# m202-stereo-input.net
KiCad netlist of a schematic drawn in EAGLE
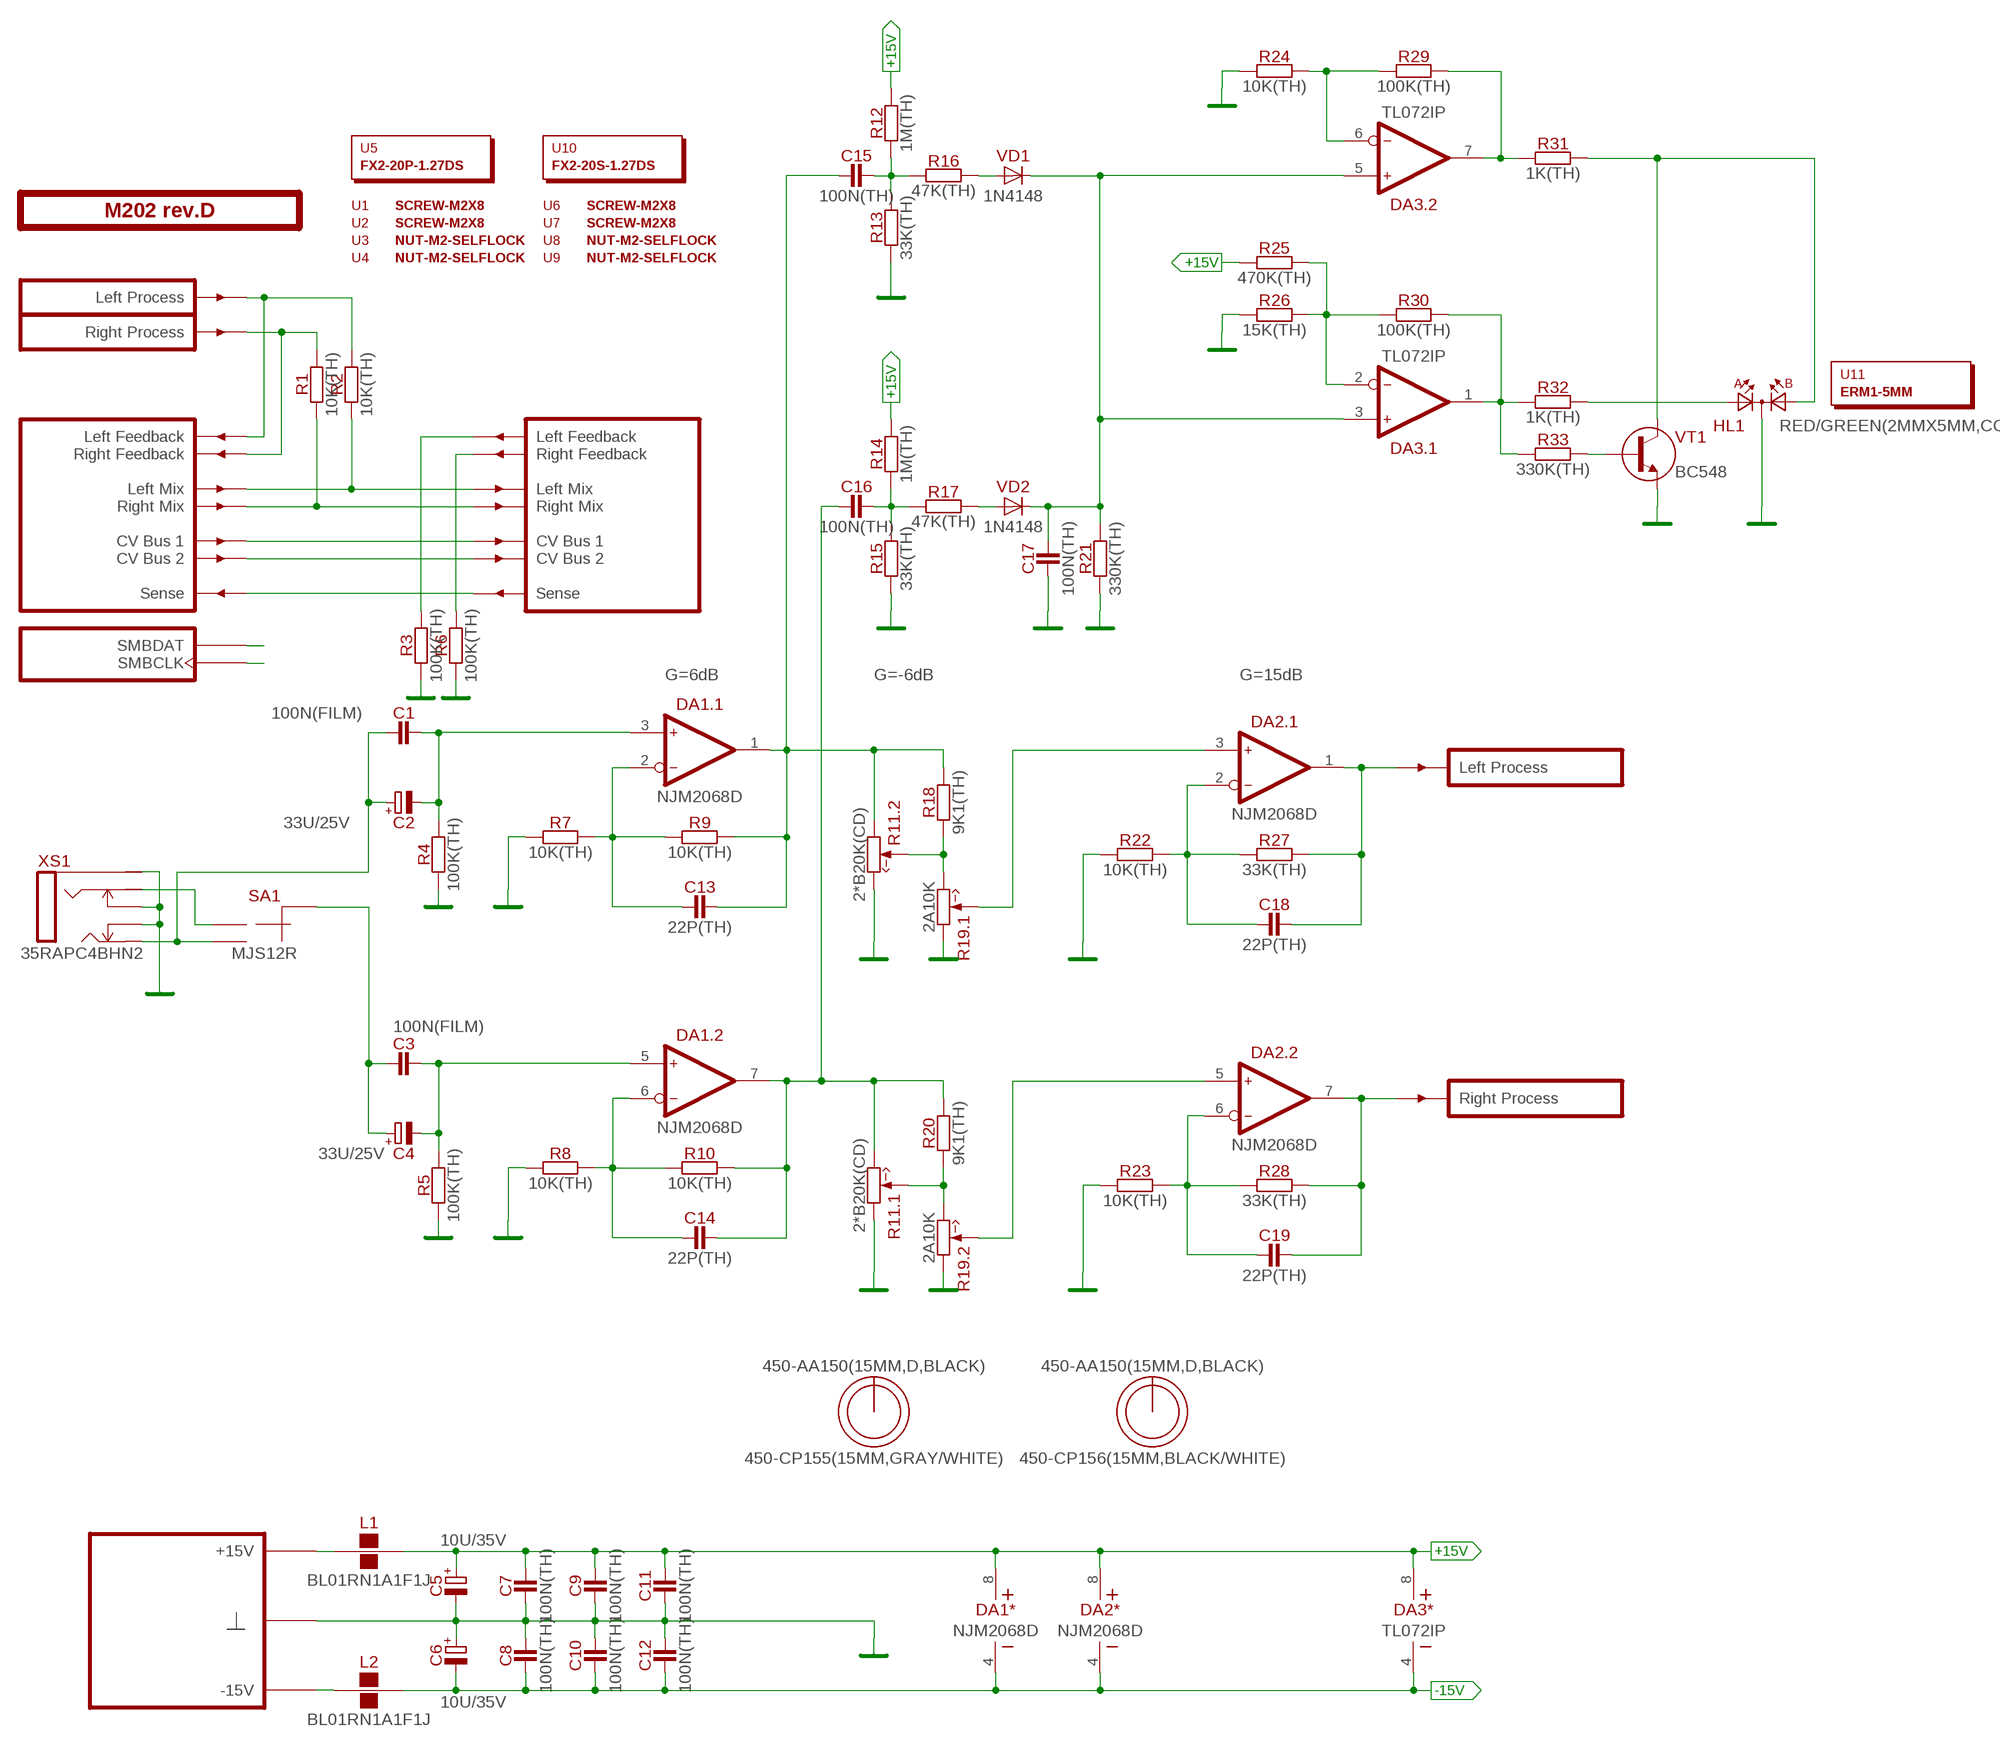
[diagram p0: schematic, sheet 1]

(export (version "E")
  (design (tool "Eeschema 10.0.6"))
  (components
    (comp (ref "C1")
      (value "100N(FILM)")
      (footprint "eagle-import:C050-025X075")
      (libsource (lib "eagle-import") (part "?100N(FILM)"))
    )
    (comp (ref "C2")
      (value "33U/25V")
      (footprint "eagle-import:E2,5-7")
      (libsource (lib "eagle-import") (part "?33U/25V"))
    )
    (comp (ref "C3")
      (value "100N(FILM)")
      (footprint "eagle-import:C050-025X075")
      (libsource (lib "eagle-import") (part "?100N(FILM)"))
    )
    (comp (ref "C4")
      (value "33U/25V")
      (footprint "eagle-import:E2,5-7")
      (libsource (lib "eagle-import") (part "?33U/25V"))
    )
    (comp (ref "C5")
      (value "10U/35V")
      (footprint "eagle-import:E2-5")
      (libsource (lib "eagle-import") (part "?10U/35V"))
    )
    (comp (ref "C6")
      (value "10U/35V")
      (footprint "eagle-import:E2-5")
      (libsource (lib "eagle-import") (part "?10U/35V"))
    )
    (comp (ref "C7")
      (value "100N(TH)")
      (footprint "eagle-import:C050-024X044")
      (libsource (lib "eagle-import") (part "?100N(TH)"))
    )
    (comp (ref "C8")
      (value "100N(TH)")
      (footprint "eagle-import:C050-024X044")
      (libsource (lib "eagle-import") (part "?100N(TH)"))
    )
    (comp (ref "C9")
      (value "100N(TH)")
      (footprint "eagle-import:C050-024X044")
      (libsource (lib "eagle-import") (part "?100N(TH)"))
    )
    (comp (ref "C10")
      (value "100N(TH)")
      (footprint "eagle-import:C050-024X044")
      (libsource (lib "eagle-import") (part "?100N(TH)"))
    )
    (comp (ref "C11")
      (value "100N(TH)")
      (footprint "eagle-import:C050-024X044")
      (libsource (lib "eagle-import") (part "?100N(TH)"))
    )
    (comp (ref "C12")
      (value "100N(TH)")
      (footprint "eagle-import:C050-024X044")
      (libsource (lib "eagle-import") (part "?100N(TH)"))
    )
    (comp (ref "C13")
      (value "22P(TH)")
      (footprint "eagle-import:C050-024X044")
      (libsource (lib "eagle-import") (part "?22P(TH)"))
    )
    (comp (ref "C14")
      (value "22P(TH)")
      (footprint "eagle-import:C050-024X044")
      (libsource (lib "eagle-import") (part "?22P(TH)"))
    )
    (comp (ref "C15")
      (value "100N(TH)")
      (footprint "eagle-import:C050-024X044")
      (libsource (lib "eagle-import") (part "?100N(TH)"))
    )
    (comp (ref "C16")
      (value "100N(TH)")
      (footprint "eagle-import:C050-024X044")
      (libsource (lib "eagle-import") (part "?100N(TH)"))
    )
    (comp (ref "C17")
      (value "100N(TH)")
      (footprint "eagle-import:C050-024X044")
      (libsource (lib "eagle-import") (part "?100N(TH)"))
    )
    (comp (ref "C18")
      (value "22P(TH)")
      (footprint "eagle-import:C050-024X044")
      (libsource (lib "eagle-import") (part "?22P(TH)"))
    )
    (comp (ref "C19")
      (value "22P(TH)")
      (footprint "eagle-import:C050-024X044")
      (libsource (lib "eagle-import") (part "?22P(TH)"))
    )
    (comp (ref "DA1")
      (value "NJM2068D")
      (footprint "eagle-import:DIP-8")
      (libsource (lib "eagle-import") (part "NJM2068D"))
    )
    (comp (ref "DA2")
      (value "NJM2068D")
      (footprint "eagle-import:DIP-8")
      (libsource (lib "eagle-import") (part "NJM2068D"))
    )
    (comp (ref "DA3")
      (value "TL072IP")
      (footprint "eagle-import:DIP-8")
      (libsource (lib "eagle-import") (part "TL072IP"))
    )
    (comp (ref "HL1")
      (value "RED/GREEN(2MMX5MM,CC)")
      (footprint "eagle-import:LED2X5-3PIN")
      (libsource (lib "eagle-import") (part "?(2MMX5MM,CC)RED/GREEN"))
    )
    (comp (ref "L1")
      (value "BL01RN1A1F1J")
      (footprint "eagle-import:BL01RN1A")
      (libsource (lib "eagle-import") (part "BL01RN1A?1F1J"))
    )
    (comp (ref "L2")
      (value "BL01RN1A1F1J")
      (footprint "eagle-import:BL01RN1A")
      (libsource (lib "eagle-import") (part "BL01RN1A?1F1J"))
    )
    (comp (ref "O1")
      (value "450-AA150(15MM,D,BLACK)")
      (footprint "eagle-import:EMPTY")
      (libsource (lib "eagle-import") (part "450-AA?150(15MM,D,BLACK)"))
    )
    (comp (ref "O2")
      (value "450-CP155(15MM,GRAY/WHITE)")
      (footprint "eagle-import:EMPTY")
      (libsource (lib "eagle-import") (part "450-C?P155(15MM,GRAY/WHITE)"))
    )
    (comp (ref "O3")
      (value "450-AA150(15MM,D,BLACK)")
      (footprint "eagle-import:EMPTY")
      (libsource (lib "eagle-import") (part "450-AA?150(15MM,D,BLACK)"))
    )
    (comp (ref "O4")
      (value "450-CP156(15MM,BLACK/WHITE)")
      (footprint "eagle-import:EMPTY")
      (libsource (lib "eagle-import") (part "450-C?P156(15MM,BLACK/WHITE)"))
    )
    (comp (ref "PCB1")
      (value "M202 rev.D")
      (footprint "eagle-import:ST2-BOARD-50")
      (libsource (lib "eagle-import") (part "ST2-BOARD-?50"))
    )
    (comp (ref "R1")
      (value "10K(TH)")
      (footprint "eagle-import:R-0207_10")
      (libsource (lib "eagle-import") (part "?10K(TH)"))
    )
    (comp (ref "R2")
      (value "10K(TH)")
      (footprint "eagle-import:R-0207_10")
      (libsource (lib "eagle-import") (part "?10K(TH)"))
    )
    (comp (ref "R3")
      (value "100K(TH)")
      (footprint "eagle-import:R-0207_10")
      (libsource (lib "eagle-import") (part "?100K(TH)"))
    )
    (comp (ref "R4")
      (value "100K(TH)")
      (footprint "eagle-import:R-0207_10")
      (libsource (lib "eagle-import") (part "?100K(TH)"))
    )
    (comp (ref "R5")
      (value "100K(TH)")
      (footprint "eagle-import:R-0207_10")
      (libsource (lib "eagle-import") (part "?100K(TH)"))
    )
    (comp (ref "R6")
      (value "100K(TH)")
      (footprint "eagle-import:R-0207_10")
      (libsource (lib "eagle-import") (part "?100K(TH)"))
    )
    (comp (ref "R7")
      (value "10K(TH)")
      (footprint "eagle-import:R-0207_10")
      (libsource (lib "eagle-import") (part "?10K(TH)"))
    )
    (comp (ref "R8")
      (value "10K(TH)")
      (footprint "eagle-import:R-0207_10")
      (libsource (lib "eagle-import") (part "?10K(TH)"))
    )
    (comp (ref "R9")
      (value "10K(TH)")
      (footprint "eagle-import:R-0207_10")
      (libsource (lib "eagle-import") (part "?10K(TH)"))
    )
    (comp (ref "R10")
      (value "10K(TH)")
      (footprint "eagle-import:R-0207_10")
      (libsource (lib "eagle-import") (part "?10K(TH)"))
    )
    (comp (ref "R11")
      (value "2*B20K(CD)")
      (footprint "eagle-import:RV11-DUAL")
      (libsource (lib "eagle-import") (part "2?B20K(CD)"))
    )
    (comp (ref "R12")
      (value "1M(TH)")
      (footprint "eagle-import:R-0207_10")
      (libsource (lib "eagle-import") (part "?1M(TH)"))
    )
    (comp (ref "R13")
      (value "33K(TH)")
      (footprint "eagle-import:R-0207_10")
      (libsource (lib "eagle-import") (part "?33K(TH)"))
    )
    (comp (ref "R14")
      (value "1M(TH)")
      (footprint "eagle-import:R-0207_10")
      (libsource (lib "eagle-import") (part "?1M(TH)"))
    )
    (comp (ref "R15")
      (value "33K(TH)")
      (footprint "eagle-import:R-0207_10")
      (libsource (lib "eagle-import") (part "?33K(TH)"))
    )
    (comp (ref "R16")
      (value "47K(TH)")
      (footprint "eagle-import:R-0207_10")
      (libsource (lib "eagle-import") (part "?47K(TH)"))
    )
    (comp (ref "R17")
      (value "47K(TH)")
      (footprint "eagle-import:R-0207_10")
      (libsource (lib "eagle-import") (part "?47K(TH)"))
    )
    (comp (ref "R18")
      (value "9K1(TH)")
      (footprint "eagle-import:R-0207_10")
      (libsource (lib "eagle-import") (part "?9K1(TH)"))
    )
    (comp (ref "R19")
      (value "2A10K")
      (footprint "eagle-import:RV11-DUAL")
      (libsource (lib "eagle-import") (part "2?A10K"))
    )
    (comp (ref "R20")
      (value "9K1(TH)")
      (footprint "eagle-import:R-0207_10")
      (libsource (lib "eagle-import") (part "?9K1(TH)"))
    )
    (comp (ref "R21")
      (value "330K(TH)")
      (footprint "eagle-import:R-0207_10")
      (libsource (lib "eagle-import") (part "?330K(TH)"))
    )
    (comp (ref "R22")
      (value "10K(TH)")
      (footprint "eagle-import:R-0207_10")
      (libsource (lib "eagle-import") (part "?10K(TH)"))
    )
    (comp (ref "R23")
      (value "10K(TH)")
      (footprint "eagle-import:R-0207_10")
      (libsource (lib "eagle-import") (part "?10K(TH)"))
    )
    (comp (ref "R24")
      (value "10K(TH)")
      (footprint "eagle-import:R-0207_10")
      (libsource (lib "eagle-import") (part "?10K(TH)"))
    )
    (comp (ref "R25")
      (value "470K(TH)")
      (footprint "eagle-import:R-0207_10")
      (libsource (lib "eagle-import") (part "?470K(TH)"))
    )
    (comp (ref "R26")
      (value "15K(TH)")
      (footprint "eagle-import:R-0207_10")
      (libsource (lib "eagle-import") (part "?15K(TH)"))
    )
    (comp (ref "R27")
      (value "33K(TH)")
      (footprint "eagle-import:R-0207_10")
      (libsource (lib "eagle-import") (part "?33K(TH)"))
    )
    (comp (ref "R28")
      (value "33K(TH)")
      (footprint "eagle-import:R-0207_10")
      (libsource (lib "eagle-import") (part "?33K(TH)"))
    )
    (comp (ref "R29")
      (value "100K(TH)")
      (footprint "eagle-import:R-0207_10")
      (libsource (lib "eagle-import") (part "?100K(TH)"))
    )
    (comp (ref "R30")
      (value "100K(TH)")
      (footprint "eagle-import:R-0207_10")
      (libsource (lib "eagle-import") (part "?100K(TH)"))
    )
    (comp (ref "R31")
      (value "1K(TH)")
      (footprint "eagle-import:R-0207_10")
      (libsource (lib "eagle-import") (part "?1K(TH)"))
    )
    (comp (ref "R32")
      (value "1K(TH)")
      (footprint "eagle-import:R-0207_10")
      (libsource (lib "eagle-import") (part "?1K(TH)"))
    )
    (comp (ref "R33")
      (value "330K(TH)")
      (footprint "eagle-import:R-0207_10")
      (libsource (lib "eagle-import") (part "?330K(TH)"))
    )
    (comp (ref "SA1")
      (value "MJS12R")
      (footprint "eagle-import:APEM-MJS12R")
      (libsource (lib "eagle-import") (part "MJS12R"))
    )
    (comp (ref "U1")
      (value "SCREW-M2X8")
      (footprint "eagle-import:EMPTY")
      (libsource (lib "eagle-import") (part "?SCREW-M2X8"))
    )
    (comp (ref "U2")
      (value "SCREW-M2X8")
      (footprint "eagle-import:EMPTY")
      (libsource (lib "eagle-import") (part "?SCREW-M2X8"))
    )
    (comp (ref "U3")
      (value "NUT-M2-SELFLOCK")
      (footprint "eagle-import:EMPTY")
      (libsource (lib "eagle-import") (part "?NUT-M2-SELFLOCK"))
    )
    (comp (ref "U4")
      (value "NUT-M2-SELFLOCK")
      (footprint "eagle-import:EMPTY")
      (libsource (lib "eagle-import") (part "?NUT-M2-SELFLOCK"))
    )
    (comp (ref "U5")
      (value "FX2-20P-1.27DS")
      (footprint "eagle-import:EMPTY")
      (libsource (lib "eagle-import") (part "?FX2-20P-1.27DS"))
    )
    (comp (ref "U6")
      (value "SCREW-M2X8")
      (footprint "eagle-import:EMPTY")
      (libsource (lib "eagle-import") (part "?SCREW-M2X8"))
    )
    (comp (ref "U7")
      (value "SCREW-M2X8")
      (footprint "eagle-import:EMPTY")
      (libsource (lib "eagle-import") (part "?SCREW-M2X8"))
    )
    (comp (ref "U8")
      (value "NUT-M2-SELFLOCK")
      (footprint "eagle-import:EMPTY")
      (libsource (lib "eagle-import") (part "?NUT-M2-SELFLOCK"))
    )
    (comp (ref "U9")
      (value "NUT-M2-SELFLOCK")
      (footprint "eagle-import:EMPTY")
      (libsource (lib "eagle-import") (part "?NUT-M2-SELFLOCK"))
    )
    (comp (ref "U10")
      (value "FX2-20S-1.27DS")
      (footprint "eagle-import:EMPTY")
      (libsource (lib "eagle-import") (part "?FX2-20S-1.27DS"))
    )
    (comp (ref "U11")
      (value "ERM1-5MM")
      (footprint "eagle-import:EMPTY")
      (libsource (lib "eagle-import") (part "?ERM1-5MM"))
    )
    (comp (ref "VD1")
      (value "1N4148")
      (footprint "eagle-import:DO35-7")
      (libsource (lib "eagle-import") (part "?1N4148"))
    )
    (comp (ref "VD2")
      (value "1N4148")
      (footprint "eagle-import:DO35-7")
      (libsource (lib "eagle-import") (part "?1N4148"))
    )
    (comp (ref "VT1")
      (value "BC548")
      (footprint "eagle-import:TO92")
      (libsource (lib "eagle-import") (part "?BC548"))
    )
    (comp (ref "XS1")
      (value "35RAPC4BHN2")
      (footprint "eagle-import:35RAP")
      (libsource (lib "eagle-import") (part "35RAPC4BHN2"))
    )
  )
  (nets
    (net (code "1") (name "+15V") (class "Default")
      (node (ref "C11") (pin "2") (pinfunction "2_2") (pintype "passive"))
      (node (ref "C5") (pin "+") (pinfunction "+_+") (pintype "passive"))
      (node (ref "C7") (pin "2") (pinfunction "2_2") (pintype "passive"))
      (node (ref "C9") (pin "2") (pinfunction "2_2") (pintype "passive"))
      (node (ref "DA1") (pin "8") (pinfunction "V+_8") (pintype "power_in"))
      (node (ref "DA2") (pin "8") (pinfunction "V+_8") (pintype "power_in"))
      (node (ref "DA3") (pin "8") (pinfunction "V+_8") (pintype "power_in"))
      (node (ref "L1") (pin "2") (pinfunction "2_2") (pintype "passive"))
      (node (ref "R12") (pin "2") (pinfunction "2_2") (pintype "passive"))
      (node (ref "R14") (pin "2") (pinfunction "2_2") (pintype "passive"))
      (node (ref "R25") (pin "1") (pinfunction "1_1") (pintype "passive"))
    )
    (net (code "2") (name "-15V") (class "Default")
      (node (ref "C10") (pin "1") (pinfunction "1_1") (pintype "passive"))
      (node (ref "C12") (pin "1") (pinfunction "1_1") (pintype "passive"))
      (node (ref "C6") (pin "-") (pinfunction "-_-") (pintype "passive"))
      (node (ref "C8") (pin "1") (pinfunction "1_1") (pintype "passive"))
      (node (ref "DA1") (pin "4") (pinfunction "V-_4") (pintype "power_in"))
      (node (ref "DA2") (pin "4") (pinfunction "V-_4") (pintype "power_in"))
      (node (ref "DA3") (pin "4") (pinfunction "V-_4") (pintype "power_in"))
      (node (ref "L2") (pin "2") (pinfunction "2_2") (pintype "passive"))
    )
    (net (code "3") (name "GND") (class "Default")
      (node (ref "C10") (pin "2") (pinfunction "2_2") (pintype "passive"))
      (node (ref "C11") (pin "1") (pinfunction "1_1") (pintype "passive"))
      (node (ref "C12") (pin "2") (pinfunction "2_2") (pintype "passive"))
      (node (ref "C17") (pin "1") (pinfunction "1_1") (pintype "passive"))
      (node (ref "C5") (pin "-") (pinfunction "-_-") (pintype "passive"))
      (node (ref "C6") (pin "+") (pinfunction "+_+") (pintype "passive"))
      (node (ref "C7") (pin "1") (pinfunction "1_1") (pintype "passive"))
      (node (ref "C8") (pin "2") (pinfunction "2_2") (pintype "passive"))
      (node (ref "C9") (pin "1") (pinfunction "1_1") (pintype "passive"))
      (node (ref "HL1") (pin "K") (pinfunction "K_K") (pintype "passive"))
      (node (ref "PCB1") (pin "B4") (pinfunction "GND_B4") (pintype "bidirectional"))
      (node (ref "PCB1") (pin "B4'") (pinfunction "GND_B4'") (pintype "bidirectional"))
      (node (ref "PCB1") (pin "B5") (pinfunction "GND_B5") (pintype "bidirectional"))
      (node (ref "PCB1") (pin "B5'") (pinfunction "GND_B5'") (pintype "bidirectional"))
      (node (ref "PCB1") (pin "B6") (pinfunction "GND_B6") (pintype "bidirectional"))
      (node (ref "PCB1") (pin "B6'") (pinfunction "GND_B6'") (pintype "bidirectional"))
      (node (ref "PCB1") (pin "B7") (pinfunction "GND_B7") (pintype "bidirectional"))
      (node (ref "PCB1") (pin "B7'") (pinfunction "GND_B7'") (pintype "bidirectional"))
      (node (ref "PCB1") (pin "B8") (pinfunction "GND_B8") (pintype "bidirectional"))
      (node (ref "PCB1") (pin "B8'") (pinfunction "GND_B8'") (pintype "bidirectional"))
      (node (ref "R11") (pin "1") (pinfunction "CCW_1") (pintype "passive"))
      (node (ref "R11") (pin "3'") (pinfunction "CW_3'") (pintype "passive"))
      (node (ref "R13") (pin "1") (pinfunction "1_1") (pintype "passive"))
      (node (ref "R15") (pin "1") (pinfunction "1_1") (pintype "passive"))
      (node (ref "R19") (pin "1") (pinfunction "CCW_1") (pintype "passive"))
      (node (ref "R19") (pin "1'") (pinfunction "CCW_1'") (pintype "passive"))
      (node (ref "R21") (pin "1") (pinfunction "1_1") (pintype "passive"))
      (node (ref "R22") (pin "1") (pinfunction "1_1") (pintype "passive"))
      (node (ref "R23") (pin "1") (pinfunction "1_1") (pintype "passive"))
      (node (ref "R24") (pin "1") (pinfunction "1_1") (pintype "passive"))
      (node (ref "R26") (pin "1") (pinfunction "1_1") (pintype "passive"))
      (node (ref "R3") (pin "1") (pinfunction "1_1") (pintype "passive"))
      (node (ref "R4") (pin "1") (pinfunction "1_1") (pintype "passive"))
      (node (ref "R5") (pin "1") (pinfunction "1_1") (pintype "passive"))
      (node (ref "R6") (pin "1") (pinfunction "1_1") (pintype "passive"))
      (node (ref "R7") (pin "1") (pinfunction "1_1") (pintype "passive"))
      (node (ref "R8") (pin "1") (pinfunction "1_1") (pintype "passive"))
      (node (ref "VT1") (pin "3") (pinfunction "E_3") (pintype "passive"))
      (node (ref "XS1") (pin "1") (pinfunction "S_1") (pintype "passive"))
      (node (ref "XS1") (pin "10") (pinfunction "TN_10") (pintype "passive"))
      (node (ref "XS1") (pin "11") (pinfunction "RN_11") (pintype "passive"))
    )
    (net (code "4") (name "Net-(C15-Pad2)") (class "Default")
      (node (ref "C15") (pin "2") (pinfunction "2_2") (pintype "passive"))
      (node (ref "R12") (pin "1") (pinfunction "1_1") (pintype "passive"))
      (node (ref "R13") (pin "2") (pinfunction "2_2") (pintype "passive"))
      (node (ref "R16") (pin "1") (pinfunction "1_1") (pintype "passive"))
    )
    (net (code "5") (name "Net-(C16-Pad2)") (class "Default")
      (node (ref "C16") (pin "2") (pinfunction "2_2") (pintype "passive"))
      (node (ref "R14") (pin "1") (pinfunction "1_1") (pintype "passive"))
      (node (ref "R15") (pin "2") (pinfunction "2_2") (pintype "passive"))
      (node (ref "R17") (pin "1") (pinfunction "1_1") (pintype "passive"))
    )
    (net (code "6") (name "Net-(DA1B-IN+)") (class "Default")
      (node (ref "C1") (pin "2") (pinfunction "2_2") (pintype "passive"))
      (node (ref "C2") (pin "-") (pinfunction "-_-") (pintype "passive"))
      (node (ref "DA1") (pin "3") (pinfunction "IN+_3") (pintype "input"))
      (node (ref "R4") (pin "2") (pinfunction "2_2") (pintype "passive"))
    )
    (net (code "7") (name "Net-(DA1B-IN-)") (class "Default")
      (node (ref "C13") (pin "1") (pinfunction "1_1") (pintype "passive"))
      (node (ref "DA1") (pin "2") (pinfunction "IN-_2") (pintype "input"))
      (node (ref "R7") (pin "2") (pinfunction "2_2") (pintype "passive"))
      (node (ref "R9") (pin "1") (pinfunction "1_1") (pintype "passive"))
    )
    (net (code "8") (name "Net-(DA1B-OUT)") (class "Default")
      (node (ref "C13") (pin "2") (pinfunction "2_2") (pintype "passive"))
      (node (ref "C15") (pin "1") (pinfunction "1_1") (pintype "passive"))
      (node (ref "DA1") (pin "1") (pinfunction "OUT_1") (pintype "output"))
      (node (ref "R11") (pin "1'") (pinfunction "CCW_1'") (pintype "passive"))
      (node (ref "R18") (pin "2") (pinfunction "2_2") (pintype "passive"))
      (node (ref "R9") (pin "2") (pinfunction "2_2") (pintype "passive"))
    )
    (net (code "9") (name "Net-(DA1C-IN+)") (class "Default")
      (node (ref "C3") (pin "2") (pinfunction "2_2") (pintype "passive"))
      (node (ref "C4") (pin "-") (pinfunction "-_-") (pintype "passive"))
      (node (ref "DA1") (pin "5") (pinfunction "IN+_5") (pintype "input"))
      (node (ref "R5") (pin "2") (pinfunction "2_2") (pintype "passive"))
    )
    (net (code "10") (name "Net-(DA1C-IN-)") (class "Default")
      (node (ref "C14") (pin "1") (pinfunction "1_1") (pintype "passive"))
      (node (ref "DA1") (pin "6") (pinfunction "IN-_6") (pintype "input"))
      (node (ref "R10") (pin "1") (pinfunction "1_1") (pintype "passive"))
      (node (ref "R8") (pin "2") (pinfunction "2_2") (pintype "passive"))
    )
    (net (code "11") (name "Net-(DA1C-OUT)") (class "Default")
      (node (ref "C14") (pin "2") (pinfunction "2_2") (pintype "passive"))
      (node (ref "C16") (pin "1") (pinfunction "1_1") (pintype "passive"))
      (node (ref "DA1") (pin "7") (pinfunction "OUT_7") (pintype "output"))
      (node (ref "R10") (pin "2") (pinfunction "2_2") (pintype "passive"))
      (node (ref "R11") (pin "3") (pinfunction "CW_3") (pintype "passive"))
      (node (ref "R20") (pin "2") (pinfunction "2_2") (pintype "passive"))
    )
    (net (code "12") (name "Net-(DA2B-IN+)") (class "Default")
      (node (ref "DA2") (pin "3") (pinfunction "IN+_3") (pintype "input"))
      (node (ref "R19") (pin "2") (pinfunction "W_2") (pintype "passive"))
    )
    (net (code "13") (name "Net-(DA2B-IN-)") (class "Default")
      (node (ref "C18") (pin "1") (pinfunction "1_1") (pintype "passive"))
      (node (ref "DA2") (pin "2") (pinfunction "IN-_2") (pintype "input"))
      (node (ref "R22") (pin "2") (pinfunction "2_2") (pintype "passive"))
      (node (ref "R27") (pin "1") (pinfunction "1_1") (pintype "passive"))
    )
    (net (code "14") (name "Net-(DA2B-OUT)") (class "Default")
      (node (ref "C18") (pin "2") (pinfunction "2_2") (pintype "passive"))
      (node (ref "DA2") (pin "1") (pinfunction "OUT_1") (pintype "output"))
      (node (ref "PCB1") (pin "BOUTL'") (pinfunction "OUTL_BOUTL'") (pintype "bidirectional"))
      (node (ref "R27") (pin "2") (pinfunction "2_2") (pintype "passive"))
    )
    (net (code "15") (name "Net-(DA2C-IN+)") (class "Default")
      (node (ref "DA2") (pin "5") (pinfunction "IN+_5") (pintype "input"))
      (node (ref "R19") (pin "2'") (pinfunction "W_2'") (pintype "passive"))
    )
    (net (code "16") (name "Net-(DA2C-IN-)") (class "Default")
      (node (ref "C19") (pin "1") (pinfunction "1_1") (pintype "passive"))
      (node (ref "DA2") (pin "6") (pinfunction "IN-_6") (pintype "input"))
      (node (ref "R23") (pin "2") (pinfunction "2_2") (pintype "passive"))
      (node (ref "R28") (pin "1") (pinfunction "1_1") (pintype "passive"))
    )
    (net (code "17") (name "Net-(DA2C-OUT)") (class "Default")
      (node (ref "C19") (pin "2") (pinfunction "2_2") (pintype "passive"))
      (node (ref "DA2") (pin "7") (pinfunction "OUT_7") (pintype "output"))
      (node (ref "PCB1") (pin "BOUTR'") (pinfunction "OUTR_BOUTR'") (pintype "bidirectional"))
      (node (ref "R28") (pin "2") (pinfunction "2_2") (pintype "passive"))
    )
    (net (code "18") (name "Net-(DA3B-IN+)") (class "Default")
      (node (ref "C17") (pin "2") (pinfunction "2_2") (pintype "passive"))
      (node (ref "DA3") (pin "3") (pinfunction "IN+_3") (pintype "input"))
      (node (ref "DA3") (pin "5") (pinfunction "IN+_5") (pintype "input"))
      (node (ref "R21") (pin "2") (pinfunction "2_2") (pintype "passive"))
      (node (ref "VD1") (pin "C") (pinfunction "C_C") (pintype "passive"))
      (node (ref "VD2") (pin "C") (pinfunction "C_C") (pintype "passive"))
    )
    (net (code "19") (name "Net-(DA3B-IN-)") (class "Default")
      (node (ref "DA3") (pin "2") (pinfunction "IN-_2") (pintype "input"))
      (node (ref "R25") (pin "2") (pinfunction "2_2") (pintype "passive"))
      (node (ref "R26") (pin "2") (pinfunction "2_2") (pintype "passive"))
      (node (ref "R30") (pin "1") (pinfunction "1_1") (pintype "passive"))
    )
    (net (code "20") (name "Net-(DA3B-OUT)") (class "Default")
      (node (ref "DA3") (pin "1") (pinfunction "OUT_1") (pintype "output"))
      (node (ref "R30") (pin "2") (pinfunction "2_2") (pintype "passive"))
      (node (ref "R32") (pin "1") (pinfunction "1_1") (pintype "passive"))
      (node (ref "R33") (pin "1") (pinfunction "1_1") (pintype "passive"))
    )
    (net (code "21") (name "Net-(DA3C-IN-)") (class "Default")
      (node (ref "DA3") (pin "6") (pinfunction "IN-_6") (pintype "input"))
      (node (ref "R24") (pin "2") (pinfunction "2_2") (pintype "passive"))
      (node (ref "R29") (pin "1") (pinfunction "1_1") (pintype "passive"))
    )
    (net (code "22") (name "Net-(DA3C-OUT)") (class "Default")
      (node (ref "DA3") (pin "7") (pinfunction "OUT_7") (pintype "output"))
      (node (ref "R29") (pin "2") (pinfunction "2_2") (pintype "passive"))
      (node (ref "R31") (pin "1") (pinfunction "1_1") (pintype "passive"))
    )
    (net (code "23") (name "Net-(HL1-PadA1)") (class "Default")
      (node (ref "HL1") (pin "A1") (pinfunction "A1_A1") (pintype "passive"))
      (node (ref "R32") (pin "2") (pinfunction "2_2") (pintype "passive"))
    )
    (net (code "24") (name "Net-(L1-Pad1)") (class "Default")
      (node (ref "L1") (pin "1") (pinfunction "1_1") (pintype "passive"))
      (node (ref "PCB1") (pin "A+15") (pinfunction "P+15V_A+15") (pintype "bidirectional"))
      (node (ref "PCB1") (pin "A+15'") (pinfunction "P+15V_A+15'") (pintype "bidirectional"))
      (node (ref "PCB1") (pin "B+15") (pinfunction "P+15V_B+15") (pintype "bidirectional"))
      (node (ref "PCB1") (pin "B+15'") (pinfunction "P+15V_B+15'") (pintype "bidirectional"))
    )
    (net (code "25") (name "Net-(L2-Pad1)") (class "Default")
      (node (ref "L2") (pin "1") (pinfunction "1_1") (pintype "passive"))
      (node (ref "PCB1") (pin "A-15") (pinfunction "P-15V_A-15") (pintype "bidirectional"))
      (node (ref "PCB1") (pin "A-15'") (pinfunction "P-15V_A-15'") (pintype "bidirectional"))
      (node (ref "PCB1") (pin "B-15") (pinfunction "P-15V_B-15") (pintype "bidirectional"))
      (node (ref "PCB1") (pin "B-15'") (pinfunction "P-15V_B-15'") (pintype "bidirectional"))
    )
    (net (code "26") (name "Net-(PCB1B-INL)") (class "Default")
      (node (ref "PCB1") (pin "ALFBK") (pinfunction "LFBK_ALFBK") (pintype "bidirectional"))
      (node (ref "PCB1") (pin "BINL") (pinfunction "INL_BINL") (pintype "bidirectional"))
      (node (ref "R2") (pin "2") (pinfunction "2_2") (pintype "passive"))
    )
    (net (code "27") (name "Net-(PCB1C-INR)") (class "Default")
      (node (ref "PCB1") (pin "ARFBK") (pinfunction "RFBK_ARFBK") (pintype "bidirectional"))
      (node (ref "PCB1") (pin "BINR") (pinfunction "INR_BINR") (pintype "bidirectional"))
      (node (ref "R1") (pin "2") (pinfunction "2_2") (pintype "passive"))
    )
    (net (code "28") (name "Net-(PCB1F-CV1)") (class "Default")
      (node (ref "PCB1") (pin "ACV1") (pinfunction "CV1_ACV1") (pintype "bidirectional"))
      (node (ref "PCB1") (pin "ACV1'") (pinfunction "CV1'_ACV1'") (pintype "bidirectional"))
    )
    (net (code "29") (name "Net-(PCB1F-CV2)") (class "Default")
      (node (ref "PCB1") (pin "ACV2") (pinfunction "CV2_ACV2") (pintype "bidirectional"))
      (node (ref "PCB1") (pin "ACV2'") (pinfunction "CV2'_ACV2'") (pintype "bidirectional"))
    )
    (net (code "30") (name "Net-(PCB1F-LMIX)") (class "Default")
      (node (ref "PCB1") (pin "ALMIX") (pinfunction "LMIX_ALMIX") (pintype "bidirectional"))
      (node (ref "PCB1") (pin "ALMIX'") (pinfunction "LMIX'_ALMIX'") (pintype "bidirectional"))
      (node (ref "R2") (pin "1") (pinfunction "1_1") (pintype "passive"))
    )
    (net (code "31") (name "Net-(PCB1F-RMIX)") (class "Default")
      (node (ref "PCB1") (pin "ARMIX") (pinfunction "RMIX_ARMIX") (pintype "bidirectional"))
      (node (ref "PCB1") (pin "ARMIX'") (pinfunction "RMIX'_ARMIX'") (pintype "bidirectional"))
      (node (ref "R1") (pin "1") (pinfunction "1_1") (pintype "passive"))
    )
    (net (code "32") (name "Net-(PCB1F-SENSE)") (class "Default")
      (node (ref "PCB1") (pin "BSENSE") (pinfunction "SENSE_BSENSE") (pintype "bidirectional"))
      (node (ref "PCB1") (pin "BSENSE'") (pinfunction "SENSE'_BSENSE'") (pintype "bidirectional"))
    )
    (net (code "33") (name "Net-(PCB1G-LFBK')") (class "Default")
      (node (ref "PCB1") (pin "ALFBK'") (pinfunction "LFBK'_ALFBK'") (pintype "bidirectional"))
      (node (ref "R3") (pin "2") (pinfunction "2_2") (pintype "passive"))
    )
    (net (code "34") (name "Net-(PCB1G-RFBK')") (class "Default")
      (node (ref "PCB1") (pin "ARFBK'") (pinfunction "RFBK'_ARFBK'") (pintype "bidirectional"))
      (node (ref "R6") (pin "2") (pinfunction "2_2") (pintype "passive"))
    )
    (net (code "35") (name "Net-(PCB1H-SMBCLK-PadASMBCLK')") (class "Default")
      (node (ref "PCB1") (pin "ASMBCLK") (pinfunction "SMBCLK_ASMBCLK") (pintype "bidirectional"))
      (node (ref "PCB1") (pin "ASMBCLK'") (pinfunction "SMBCLK_ASMBCLK'") (pintype "bidirectional"))
    )
    (net (code "36") (name "Net-(PCB1H-SMBDAT-PadASMBDAT')") (class "Default")
      (node (ref "PCB1") (pin "ASMBDAT") (pinfunction "SMBDAT_ASMBDAT") (pintype "bidirectional"))
      (node (ref "PCB1") (pin "ASMBDAT'") (pinfunction "SMBDAT_ASMBDAT'") (pintype "bidirectional"))
    )
    (net (code "37") (name "Net-(R11A-W)") (class "Default")
      (node (ref "R11") (pin "2") (pinfunction "W_2") (pintype "passive"))
      (node (ref "R19") (pin "3'") (pinfunction "CW_3'") (pintype "passive"))
      (node (ref "R20") (pin "1") (pinfunction "1_1") (pintype "passive"))
    )
    (net (code "38") (name "Net-(R11B-W)") (class "Default")
      (node (ref "R11") (pin "2'") (pinfunction "W_2'") (pintype "passive"))
      (node (ref "R18") (pin "1") (pinfunction "1_1") (pintype "passive"))
      (node (ref "R19") (pin "3") (pinfunction "CW_3") (pintype "passive"))
    )
    (net (code "39") (name "Net-(R16-Pad2)") (class "Default")
      (node (ref "R16") (pin "2") (pinfunction "2_2") (pintype "passive"))
      (node (ref "VD1") (pin "A") (pinfunction "A_A") (pintype "passive"))
    )
    (net (code "40") (name "Net-(R17-Pad2)") (class "Default")
      (node (ref "R17") (pin "2") (pinfunction "2_2") (pintype "passive"))
      (node (ref "VD2") (pin "A") (pinfunction "A_A") (pintype "passive"))
    )
    (net (code "41") (name "Net-(SA1-1)") (class "Default")
      (node (ref "SA1") (pin "NC") (pinfunction "1_NC") (pintype "passive"))
      (node (ref "XS1") (pin "3") (pinfunction "R_3") (pintype "passive"))
    )
    (net (code "42") (name "Net-(SA1-2)") (class "Default")
      (node (ref "C1") (pin "1") (pinfunction "1_1") (pintype "passive"))
      (node (ref "C2") (pin "+") (pinfunction "+_+") (pintype "passive"))
      (node (ref "SA1") (pin "NO") (pinfunction "2_NO") (pintype "passive"))
      (node (ref "XS1") (pin "2") (pinfunction "T_2") (pintype "passive"))
    )
    (net (code "43") (name "Net-(SA1-CM)") (class "Default")
      (node (ref "C3") (pin "1") (pinfunction "1_1") (pintype "passive"))
      (node (ref "C4") (pin "+") (pinfunction "+_+") (pintype "passive"))
      (node (ref "SA1") (pin "C") (pinfunction "CM_C") (pintype "passive"))
    )
    (net (code "44") (name "Net-(VT1-B)") (class "Default")
      (node (ref "R33") (pin "2") (pinfunction "2_2") (pintype "passive"))
      (node (ref "VT1") (pin "2") (pinfunction "B_2") (pintype "passive"))
    )
    (net (code "45") (name "Net-(VT1-C)") (class "Default")
      (node (ref "HL1") (pin "A2") (pinfunction "A2_A2") (pintype "passive"))
      (node (ref "R31") (pin "2") (pinfunction "2_2") (pintype "passive"))
      (node (ref "VT1") (pin "1") (pinfunction "C_1") (pintype "passive"))
    )
  )
)
